# 12V_Input_Circuitry.net
KiCad netlist of a schematic drawn in Altium Designer
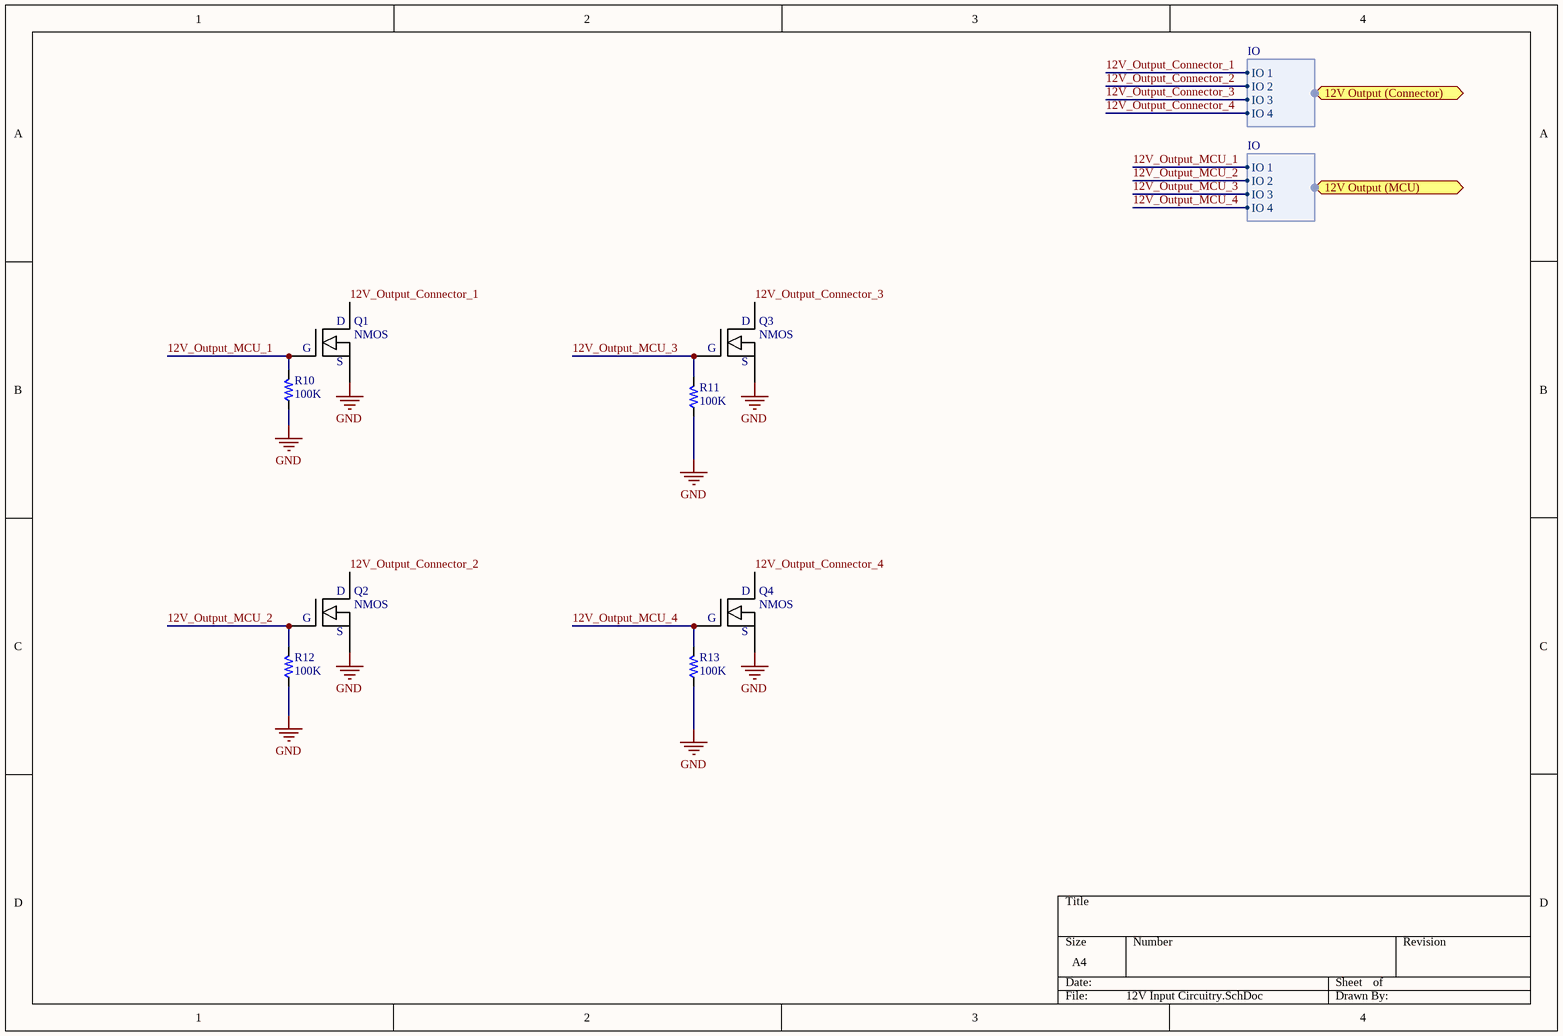
[diagram p0: 12V Input Circuitry.SchDoc]

(export (version "E")
  (design (tool "Eeschema 10.0.6"))
  (components
    (comp (ref "Q1")
      (value "NMOS")
      (footprint "NMOS - SSM3K333R - SOTFL95P180X88-3M")
      (libsource (lib "NMOS - SSM3K333R - SOTFL95P180X88-3M") (part "NMOS - SSM3K333R"))
    )
    (comp (ref "Q2")
      (value "NMOS")
      (footprint "NMOS - SSM3K333R - SOTFL95P180X88-3M")
      (libsource (lib "NMOS - SSM3K333R - SOTFL95P180X88-3M") (part "NMOS - SSM3K333R"))
    )
    (comp (ref "Q3")
      (value "NMOS")
      (footprint "NMOS - SSM3K333R - SOTFL95P180X88-3M")
      (libsource (lib "NMOS - SSM3K333R - SOTFL95P180X88-3M") (part "NMOS - SSM3K333R"))
    )
    (comp (ref "Q4")
      (value "NMOS")
      (footprint "NMOS - SSM3K333R - SOTFL95P180X88-3M")
      (libsource (lib "NMOS - SSM3K333R - SOTFL95P180X88-3M") (part "NMOS - SSM3K333R"))
    )
    (comp (ref "R10")
      (value "100K")
      (footprint "PCB_GENERIC_SMD_0603")
      (description "RES 0603 100K 5% 63mW")
      (fields (field (name "TOLERANCE") "5%") (field (name "POWER") "63mW"))
      (libsource (lib "RES-0603") (part "R060-00104-05"))
    )
    (comp (ref "R11")
      (value "100K")
      (footprint "PCB_GENERIC_SMD_0603")
      (description "RES 0603 100K 5% 63mW")
      (fields (field (name "TOLERANCE") "5%") (field (name "POWER") "63mW"))
      (libsource (lib "RES-0603") (part "R060-00104-05"))
    )
    (comp (ref "R12")
      (value "100K")
      (footprint "PCB_GENERIC_SMD_0603")
      (description "RES 0603 100K 5% 63mW")
      (fields (field (name "TOLERANCE") "5%") (field (name "POWER") "63mW"))
      (libsource (lib "RES-0603") (part "R060-00104-05"))
    )
    (comp (ref "R13")
      (value "100K")
      (footprint "PCB_GENERIC_SMD_0603")
      (description "RES 0603 100K 5% 63mW")
      (fields (field (name "TOLERANCE") "5%") (field (name "POWER") "63mW"))
      (libsource (lib "RES-0603") (part "R060-00104-05"))
    )
  )
  (nets
    (net (code "2") (name "/12V_Output_Connector_1") (class "Default")
      (node (ref "Q1") (pin "3") (pinfunction "D_3") (pintype "passive"))
    )
    (net (code "3") (name "/12V_Output_Connector_2") (class "Default")
      (node (ref "Q2") (pin "3") (pinfunction "D_3") (pintype "passive"))
    )
    (net (code "4") (name "/12V_Output_Connector_3") (class "Default")
      (node (ref "Q3") (pin "3") (pinfunction "D_3") (pintype "passive"))
    )
    (net (code "5") (name "/12V_Output_Connector_4") (class "Default")
      (node (ref "Q4") (pin "3") (pinfunction "D_3") (pintype "passive"))
    )
    (net (code "6") (name "/12V_Output_MCU_1") (class "Default")
      (node (ref "Q1") (pin "1") (pinfunction "G_1") (pintype "passive"))
      (node (ref "R10") (pin "2") (pinfunction "2_2") (pintype "passive"))
    )
    (net (code "7") (name "/12V_Output_MCU_2") (class "Default")
      (node (ref "Q2") (pin "1") (pinfunction "G_1") (pintype "passive"))
      (node (ref "R12") (pin "2") (pinfunction "2_2") (pintype "passive"))
    )
    (net (code "8") (name "/12V_Output_MCU_3") (class "Default")
      (node (ref "Q3") (pin "1") (pinfunction "G_1") (pintype "passive"))
      (node (ref "R11") (pin "2") (pinfunction "2_2") (pintype "passive"))
    )
    (net (code "9") (name "/12V_Output_MCU_4") (class "Default")
      (node (ref "Q4") (pin "1") (pinfunction "G_1") (pintype "passive"))
      (node (ref "R13") (pin "2") (pinfunction "2_2") (pintype "passive"))
    )
    (net (code "11") (name "GND") (class "Default")
      (node (ref "Q1") (pin "2") (pinfunction "S_2") (pintype "passive"))
      (node (ref "Q2") (pin "2") (pinfunction "S_2") (pintype "passive"))
      (node (ref "Q3") (pin "2") (pinfunction "S_2") (pintype "passive"))
      (node (ref "Q4") (pin "2") (pinfunction "S_2") (pintype "passive"))
      (node (ref "R10") (pin "1") (pinfunction "1_1") (pintype "passive"))
      (node (ref "R11") (pin "1") (pinfunction "1_1") (pintype "passive"))
      (node (ref "R12") (pin "1") (pinfunction "1_1") (pintype "passive"))
      (node (ref "R13") (pin "1") (pinfunction "1_1") (pintype "passive"))
    )
  )
)
